# glitch_delay.net
KiCad netlist of a schematic drawn in EAGLE
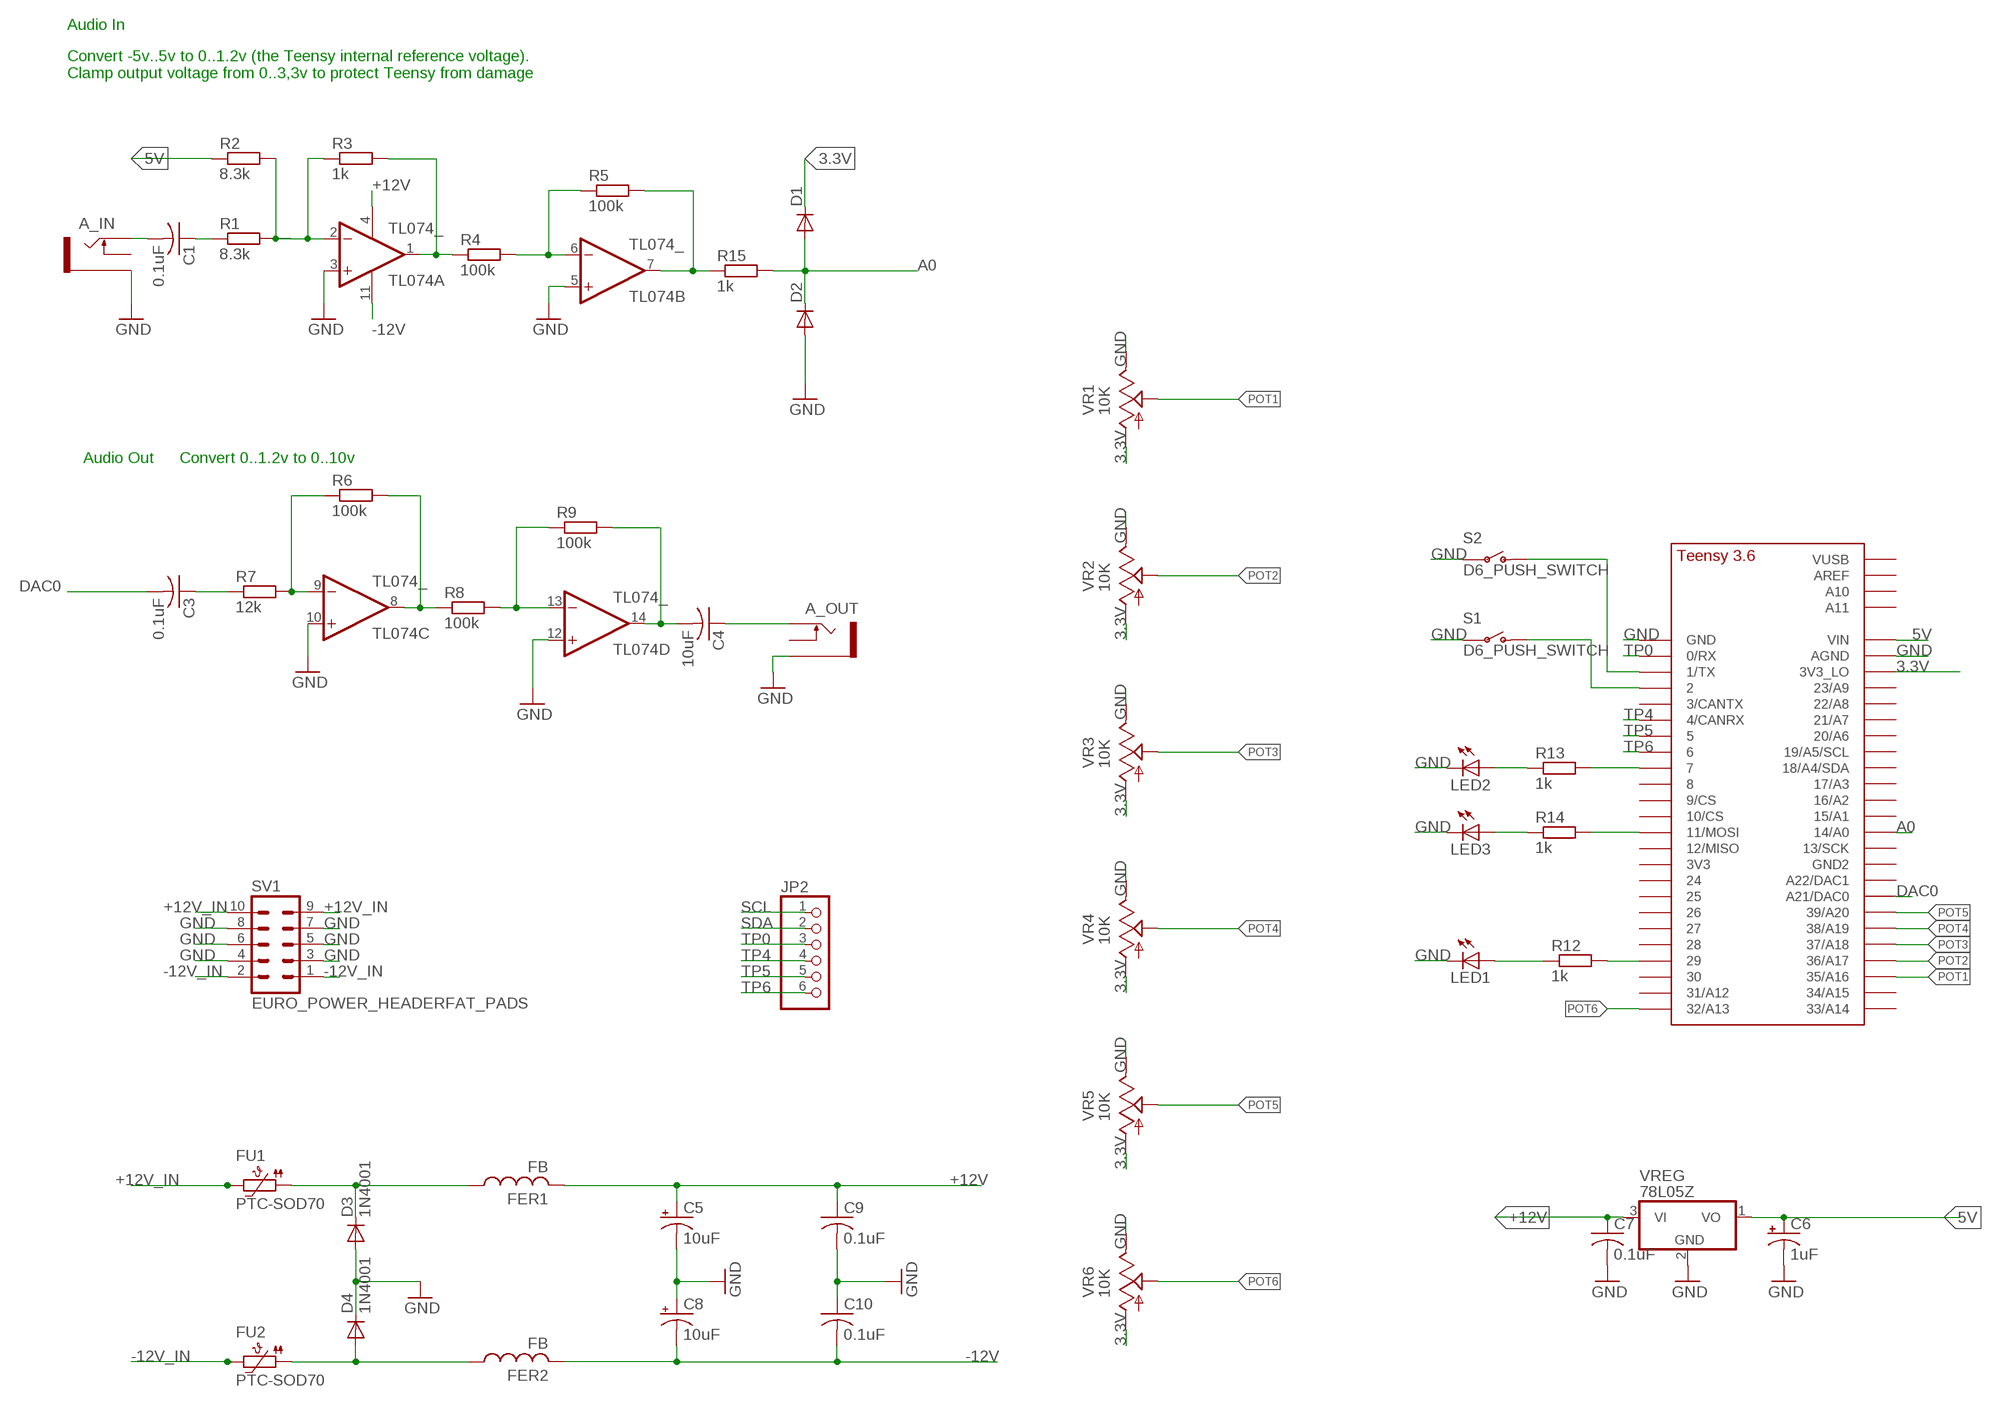
[diagram p0: schematic, sheet 1]

(export (version "E")
  (design (tool "Eeschema 10.0.6"))
  (components
    (comp (ref "A_IN")
      (value "THONKICONNNEW")
      (footprint "eagle-import:WQP-PJ301M-12_JACK")
      (libsource (lib "eagle-import") (part "THONKICONNNEW"))
    )
    (comp (ref "A_OUT")
      (value "THONKICONNNEW")
      (footprint "eagle-import:WQP-PJ301M-12_JACK")
      (libsource (lib "eagle-import") (part "THONKICONNNEW"))
    )
    (comp (ref "C1")
      (value "0.1uF")
      (footprint "eagle-import:C025-030X050")
      (libsource (lib "eagle-import") (part "C-US025-030X050"))
    )
    (comp (ref "C3")
      (value "0.1uF")
      (footprint "eagle-import:C025-030X050")
      (libsource (lib "eagle-import") (part "C-US025-030X050"))
    )
    (comp (ref "C4")
      (value "10uF")
      (footprint "eagle-import:C025-030X050")
      (libsource (lib "eagle-import") (part "C-US025-030X050"))
    )
    (comp (ref "C5")
      (value "10uF")
      (footprint "eagle-import:E2,5-6E")
      (libsource (lib "eagle-import") (part "CPOL-USE2,5-6E"))
    )
    (comp (ref "C6")
      (value "1uF")
      (footprint "eagle-import:E2,5-7")
      (libsource (lib "eagle-import") (part "CPOL-USE2.5-7"))
    )
    (comp (ref "C7")
      (value "0.1uF")
      (footprint "eagle-import:C025-030X050")
      (libsource (lib "eagle-import") (part "C-US025-030X050"))
    )
    (comp (ref "C8")
      (value "10uF")
      (footprint "eagle-import:E2,5-6E")
      (libsource (lib "eagle-import") (part "CPOL-USE2,5-6E"))
    )
    (comp (ref "C9")
      (value "0.1uF")
      (footprint "eagle-import:C025-030X050")
      (libsource (lib "eagle-import") (part "C-US025-030X050"))
    )
    (comp (ref "C10")
      (value "0.1uF")
      (footprint "eagle-import:C025-030X050")
      (libsource (lib "eagle-import") (part "C-US025-030X050"))
    )
    (comp (ref "D1")
      (value "SMALL_DIODEDO35-7")
      (footprint "eagle-import:DO35-7")
      (libsource (lib "eagle-import") (part "SMALL_DIODEDO35-7"))
    )
    (comp (ref "D2")
      (value "SMALL_DIODEDO35-7")
      (footprint "eagle-import:DO35-7")
      (libsource (lib "eagle-import") (part "SMALL_DIODEDO35-7"))
    )
    (comp (ref "D3")
      (value "1N4001")
      (footprint "eagle-import:DO41-10")
      (libsource (lib "eagle-import") (part "1N4004"))
    )
    (comp (ref "D4")
      (value "1N4001")
      (footprint "eagle-import:DO41-10")
      (libsource (lib "eagle-import") (part "1N4004"))
    )
    (comp (ref "FER1")
      (value "FB")
      (footprint "eagle-import:FB")
      (libsource (lib "eagle-import") (part "FB"))
    )
    (comp (ref "FER2")
      (value "FB")
      (footprint "eagle-import:FB")
      (libsource (lib "eagle-import") (part "FB"))
    )
    (comp (ref "FU1")
      (value "PTC-SOD70")
      (footprint "eagle-import:SOD70")
      (libsource (lib "eagle-import") (part "PTC-SOD70"))
    )
    (comp (ref "FU2")
      (value "PTC-SOD70")
      (footprint "eagle-import:SOD70")
      (libsource (lib "eagle-import") (part "PTC-SOD70"))
    )
    (comp (ref "JP2")
      (value "PINHD-1X6")
      (footprint "eagle-import:1X06")
      (libsource (lib "eagle-import") (part "PINHD-1X6"))
    )
    (comp (ref "LED1")
      (value "LED3MM")
      (footprint "eagle-import:LED3MM")
      (libsource (lib "eagle-import") (part "LED3MM"))
    )
    (comp (ref "LED2")
      (value "LED3MM")
      (footprint "eagle-import:LED3MM")
      (libsource (lib "eagle-import") (part "LED3MM"))
    )
    (comp (ref "LED3")
      (value "LED3MM")
      (footprint "eagle-import:LED3MM")
      (libsource (lib "eagle-import") (part "LED3MM"))
    )
    (comp (ref "R1")
      (value "8.3k")
      (footprint "eagle-import:7MM_RESISTOR")
      (libsource (lib "eagle-import") (part "RESISTOR7MM"))
    )
    (comp (ref "R2")
      (value "8.3k")
      (footprint "eagle-import:7MM_RESISTOR")
      (libsource (lib "eagle-import") (part "RESISTOR7MM"))
    )
    (comp (ref "R3")
      (value "1k")
      (footprint "eagle-import:7MM_RESISTOR")
      (libsource (lib "eagle-import") (part "RESISTOR7MM"))
    )
    (comp (ref "R4")
      (value "100k")
      (footprint "eagle-import:7MM_RESISTOR")
      (libsource (lib "eagle-import") (part "RESISTOR7MM"))
    )
    (comp (ref "R5")
      (value "100k")
      (footprint "eagle-import:7MM_RESISTOR")
      (libsource (lib "eagle-import") (part "RESISTOR7MM"))
    )
    (comp (ref "R6")
      (value "100k")
      (footprint "eagle-import:7MM_RESISTOR")
      (libsource (lib "eagle-import") (part "RESISTOR7MM"))
    )
    (comp (ref "R7")
      (value "12k")
      (footprint "eagle-import:7MM_RESISTOR")
      (libsource (lib "eagle-import") (part "RESISTOR7MM"))
    )
    (comp (ref "R8")
      (value "100k")
      (footprint "eagle-import:7MM_RESISTOR")
      (libsource (lib "eagle-import") (part "RESISTOR7MM"))
    )
    (comp (ref "R9")
      (value "100k")
      (footprint "eagle-import:7MM_RESISTOR")
      (libsource (lib "eagle-import") (part "RESISTOR7MM"))
    )
    (comp (ref "R12")
      (value "1k")
      (footprint "eagle-import:7MM_RESISTOR")
      (libsource (lib "eagle-import") (part "RESISTOR7MM"))
    )
    (comp (ref "R13")
      (value "1k")
      (footprint "eagle-import:7MM_RESISTOR")
      (libsource (lib "eagle-import") (part "RESISTOR7MM"))
    )
    (comp (ref "R14")
      (value "1k")
      (footprint "eagle-import:7MM_RESISTOR")
      (libsource (lib "eagle-import") (part "RESISTOR7MM"))
    )
    (comp (ref "R15")
      (value "1k")
      (footprint "eagle-import:7MM_RESISTOR")
      (libsource (lib "eagle-import") (part "RESISTOR7MM"))
    )
    (comp (ref "S1")
      (value "D6_PUSH_SWITCH")
      (footprint "eagle-import:D6_PUSH_SWITCH")
      (libsource (lib "eagle-import") (part "D6_PUSH_SWITCH"))
    )
    (comp (ref "S2")
      (value "D6_PUSH_SWITCH")
      (footprint "eagle-import:D6_PUSH_SWITCH")
      (libsource (lib "eagle-import") (part "D6_PUSH_SWITCH"))
    )
    (comp (ref "SV1")
      (value "EURO_POWER_HEADERFAT_PADS")
      (footprint "eagle-import:EURO_PWR_HEADER_FAT")
      (libsource (lib "eagle-import") (part "EURO_POWER_HEADERFAT_PADS"))
    )
    (comp (ref "TL074")
      (value "TL074_")
      (footprint "eagle-import:DIL14")
      (libsource (lib "eagle-import") (part "TL074_"))
    )
    (comp (ref "U$1")
      (value "TEENSY_3.5/3.6_BASIC")
      (footprint "eagle-import:TEENSY_3.5_3.6_BASIC")
      (libsource (lib "eagle-import") (part "TEENSY_3.5/3.6_BASIC"))
    )
    (comp (ref "VR1")
      (value "10K")
      (footprint "eagle-import:9MM_SNAP-IN_POT")
      (libsource (lib "eagle-import") (part "9MM_SNAP-IN_POT_"))
    )
    (comp (ref "VR2")
      (value "10K")
      (footprint "eagle-import:9MM_SNAP-IN_POT")
      (libsource (lib "eagle-import") (part "9MM_SNAP-IN_POT_"))
    )
    (comp (ref "VR3")
      (value "10K")
      (footprint "eagle-import:9MM_SNAP-IN_POT")
      (libsource (lib "eagle-import") (part "9MM_SNAP-IN_POT_"))
    )
    (comp (ref "VR4")
      (value "10K")
      (footprint "eagle-import:9MM_SNAP-IN_POT")
      (libsource (lib "eagle-import") (part "9MM_SNAP-IN_POT_"))
    )
    (comp (ref "VR5")
      (value "10K")
      (footprint "eagle-import:9MM_SNAP-IN_POT")
      (libsource (lib "eagle-import") (part "9MM_SNAP-IN_POT_"))
    )
    (comp (ref "VR6")
      (value "10K")
      (footprint "eagle-import:9MM_SNAP-IN_POT")
      (libsource (lib "eagle-import") (part "9MM_SNAP-IN_POT_"))
    )
    (comp (ref "VREG")
      (value "78L05Z")
      (footprint "eagle-import:TO92")
      (libsource (lib "eagle-import") (part "78ZL05"))
    )
  )
  (nets
    (net (code "1") (name "+12V") (class "Default")
      (node (ref "C5") (pin "+") (pinfunction "+_+") (pintype "passive"))
      (node (ref "C7") (pin "1") (pinfunction "1_1") (pintype "passive"))
      (node (ref "C9") (pin "1") (pinfunction "1_1") (pintype "passive"))
      (node (ref "FER1") (pin "P$2") (pinfunction "2_P$2") (pintype "passive"))
      (node (ref "TL074") (pin "4") (pinfunction "V+_4") (pintype "power_in"))
      (node (ref "VREG") (pin "3") (pinfunction "VI_3") (pintype "input"))
    )
    (net (code "2") (name "/+12V_IN") (class "Default")
      (node (ref "FU1") (pin "2") (pinfunction "2_2") (pintype "passive"))
      (node (ref "SV1") (pin "10") (pinfunction "10_10") (pintype "passive"))
      (node (ref "SV1") (pin "9") (pinfunction "9_9") (pintype "passive"))
    )
    (net (code "3") (name "/-12V") (class "Default")
      (node (ref "C10") (pin "2") (pinfunction "2_2") (pintype "passive"))
      (node (ref "C8") (pin "-") (pinfunction "-_-") (pintype "passive"))
      (node (ref "FER2") (pin "P$2") (pinfunction "2_P$2") (pintype "passive"))
      (node (ref "TL074") (pin "11") (pinfunction "V-_11") (pintype "power_in"))
    )
    (net (code "4") (name "/-12V_IN") (class "Default")
      (node (ref "FU2") (pin "2") (pinfunction "2_2") (pintype "passive"))
      (node (ref "SV1") (pin "1") (pinfunction "1_1") (pintype "passive"))
      (node (ref "SV1") (pin "2") (pinfunction "2_2") (pintype "passive"))
    )
    (net (code "5") (name "/A0") (class "Default")
      (node (ref "D1") (pin "A") (pinfunction "A_A") (pintype "passive"))
      (node (ref "D2") (pin "C") (pinfunction "C_C") (pintype "passive"))
      (node (ref "R15") (pin "2") (pinfunction "2_2") (pintype "passive"))
      (node (ref "U$1") (pin "14/A0") (pinfunction "14/A0_14/A0") (pintype "bidirectional"))
    )
    (net (code "6") (name "/DAC0") (class "Default")
      (node (ref "C3") (pin "2") (pinfunction "2_2") (pintype "passive"))
      (node (ref "U$1") (pin "21/DAC0") (pinfunction "A21/DAC0_21/DAC0") (pintype "bidirectional"))
    )
    (net (code "7") (name "/SCL") (class "Default")
      (node (ref "JP2") (pin "1") (pinfunction "1_1") (pintype "passive"))
    )
    (net (code "8") (name "/SDA") (class "Default")
      (node (ref "JP2") (pin "2") (pinfunction "2_2") (pintype "passive"))
    )
    (net (code "9") (name "/TP0") (class "Default")
      (node (ref "JP2") (pin "3") (pinfunction "3_3") (pintype "passive"))
      (node (ref "U$1") (pin "0/RX") (pinfunction "0/RX_0/RX") (pintype "bidirectional"))
    )
    (net (code "10") (name "/TP4") (class "Default")
      (node (ref "JP2") (pin "4") (pinfunction "4_4") (pintype "passive"))
      (node (ref "U$1") (pin "4/CANRX") (pinfunction "4/CANRX_4/CANRX") (pintype "bidirectional"))
    )
    (net (code "11") (name "/TP5") (class "Default")
      (node (ref "JP2") (pin "5") (pinfunction "5_5") (pintype "passive"))
      (node (ref "U$1") (pin "5") (pinfunction "5_5") (pintype "bidirectional"))
    )
    (net (code "12") (name "/TP6") (class "Default")
      (node (ref "JP2") (pin "6") (pinfunction "6_6") (pintype "passive"))
      (node (ref "U$1") (pin "6") (pinfunction "6_6") (pintype "bidirectional"))
    )
    (net (code "13") (name "3.3V") (class "Default")
      (node (ref "D1") (pin "C") (pinfunction "C_C") (pintype "passive"))
      (node (ref "U$1") (pin "3V3_LO") (pinfunction "3V3_LO_3V3_LO") (pintype "bidirectional"))
      (node (ref "VR1") (pin "1") (pinfunction "A_1") (pintype "passive"))
      (node (ref "VR2") (pin "1") (pinfunction "A_1") (pintype "passive"))
      (node (ref "VR3") (pin "1") (pinfunction "A_1") (pintype "passive"))
      (node (ref "VR4") (pin "1") (pinfunction "A_1") (pintype "passive"))
      (node (ref "VR5") (pin "1") (pinfunction "A_1") (pintype "passive"))
      (node (ref "VR6") (pin "1") (pinfunction "A_1") (pintype "passive"))
    )
    (net (code "14") (name "5V") (class "Default")
      (node (ref "C6") (pin "+") (pinfunction "+_+") (pintype "passive"))
      (node (ref "R2") (pin "1") (pinfunction "1_1") (pintype "passive"))
      (node (ref "U$1") (pin "VIN") (pinfunction "VIN_VIN") (pintype "bidirectional"))
      (node (ref "VREG") (pin "1") (pinfunction "VO_1") (pintype "passive"))
    )
    (net (code "15") (name "GND") (class "Default")
      (node (ref "A_IN") (pin "P$3_SLEEVE") (pinfunction "SLEEVE_P$3_SLEEVE") (pintype "passive"))
      (node (ref "A_OUT") (pin "P$3_SLEEVE") (pinfunction "SLEEVE_P$3_SLEEVE") (pintype "passive"))
      (node (ref "C10") (pin "1") (pinfunction "1_1") (pintype "passive"))
      (node (ref "C5") (pin "-") (pinfunction "-_-") (pintype "passive"))
      (node (ref "C6") (pin "-") (pinfunction "-_-") (pintype "passive"))
      (node (ref "C7") (pin "2") (pinfunction "2_2") (pintype "passive"))
      (node (ref "C8") (pin "+") (pinfunction "+_+") (pintype "passive"))
      (node (ref "C9") (pin "2") (pinfunction "2_2") (pintype "passive"))
      (node (ref "D2") (pin "A") (pinfunction "A_A") (pintype "passive"))
      (node (ref "D3") (pin "A") (pinfunction "A_A") (pintype "passive"))
      (node (ref "D4") (pin "C") (pinfunction "C_C") (pintype "passive"))
      (node (ref "LED1") (pin "K") (pinfunction "C_K") (pintype "passive"))
      (node (ref "LED2") (pin "K") (pinfunction "C_K") (pintype "passive"))
      (node (ref "LED3") (pin "K") (pinfunction "C_K") (pintype "passive"))
      (node (ref "S1") (pin "P$3") (pinfunction "P_P$3") (pintype "passive"))
      (node (ref "S1") (pin "P$4") (pinfunction "P_P$4") (pintype "passive"))
      (node (ref "S2") (pin "P$3") (pinfunction "P_P$3") (pintype "passive"))
      (node (ref "S2") (pin "P$4") (pinfunction "P_P$4") (pintype "passive"))
      (node (ref "SV1") (pin "3") (pinfunction "3_3") (pintype "passive"))
      (node (ref "SV1") (pin "4") (pinfunction "4_4") (pintype "passive"))
      (node (ref "SV1") (pin "5") (pinfunction "5_5") (pintype "passive"))
      (node (ref "SV1") (pin "6") (pinfunction "6_6") (pintype "passive"))
      (node (ref "SV1") (pin "7") (pinfunction "7_7") (pintype "passive"))
      (node (ref "SV1") (pin "8") (pinfunction "8_8") (pintype "passive"))
      (node (ref "TL074") (pin "10") (pinfunction "+IN_10") (pintype "input"))
      (node (ref "TL074") (pin "12") (pinfunction "+IN_12") (pintype "input"))
      (node (ref "TL074") (pin "3") (pinfunction "+IN_3") (pintype "input"))
      (node (ref "TL074") (pin "5") (pinfunction "+IN_5") (pintype "input"))
      (node (ref "U$1") (pin "AGND") (pinfunction "AGND_AGND") (pintype "bidirectional"))
      (node (ref "U$1") (pin "GND") (pinfunction "GND_GND") (pintype "bidirectional"))
      (node (ref "VR1") (pin "3") (pinfunction "E_3") (pintype "passive"))
      (node (ref "VR2") (pin "3") (pinfunction "E_3") (pintype "passive"))
      (node (ref "VR3") (pin "3") (pinfunction "E_3") (pintype "passive"))
      (node (ref "VR4") (pin "3") (pinfunction "E_3") (pintype "passive"))
      (node (ref "VR5") (pin "3") (pinfunction "E_3") (pintype "passive"))
      (node (ref "VR6") (pin "3") (pinfunction "E_3") (pintype "passive"))
      (node (ref "VREG") (pin "2") (pinfunction "GND_2") (pintype "passive"))
    )
    (net (code "16") (name "Net-(A_IN-TIP)") (class "Default")
      (node (ref "A_IN") (pin "P$1_TIP") (pinfunction "TIP_P$1_TIP") (pintype "passive"))
      (node (ref "C1") (pin "2") (pinfunction "2_2") (pintype "passive"))
    )
    (net (code "17") (name "Net-(A_OUT-TIP)") (class "Default")
      (node (ref "A_OUT") (pin "P$1_TIP") (pinfunction "TIP_P$1_TIP") (pintype "passive"))
      (node (ref "C4") (pin "1") (pinfunction "1_1") (pintype "passive"))
    )
    (net (code "18") (name "Net-(C1-Pad1)") (class "Default")
      (node (ref "C1") (pin "1") (pinfunction "1_1") (pintype "passive"))
      (node (ref "R1") (pin "1") (pinfunction "1_1") (pintype "passive"))
    )
    (net (code "19") (name "Net-(C3-Pad1)") (class "Default")
      (node (ref "C3") (pin "1") (pinfunction "1_1") (pintype "passive"))
      (node (ref "R7") (pin "1") (pinfunction "1_1") (pintype "passive"))
    )
    (net (code "20") (name "Net-(FER1-1)") (class "Default")
      (node (ref "D3") (pin "C") (pinfunction "C_C") (pintype "passive"))
      (node (ref "FER1") (pin "P$1") (pinfunction "1_P$1") (pintype "passive"))
      (node (ref "FU1") (pin "1") (pinfunction "1_1") (pintype "passive"))
    )
    (net (code "21") (name "Net-(FER2-1)") (class "Default")
      (node (ref "D4") (pin "A") (pinfunction "A_A") (pintype "passive"))
      (node (ref "FER2") (pin "P$1") (pinfunction "1_P$1") (pintype "passive"))
      (node (ref "FU2") (pin "1") (pinfunction "1_1") (pintype "passive"))
    )
    (net (code "22") (name "Net-(LED1-PadA)") (class "Default")
      (node (ref "LED1") (pin "A") (pinfunction "A_A") (pintype "passive"))
      (node (ref "R12") (pin "1") (pinfunction "1_1") (pintype "passive"))
    )
    (net (code "23") (name "Net-(LED2-PadA)") (class "Default")
      (node (ref "LED2") (pin "A") (pinfunction "A_A") (pintype "passive"))
      (node (ref "R13") (pin "1") (pinfunction "1_1") (pintype "passive"))
    )
    (net (code "24") (name "Net-(LED3-PadA)") (class "Default")
      (node (ref "LED3") (pin "A") (pinfunction "A_A") (pintype "passive"))
      (node (ref "R14") (pin "1") (pinfunction "1_1") (pintype "passive"))
    )
    (net (code "25") (name "Net-(R12-Pad2)") (class "Default")
      (node (ref "R12") (pin "2") (pinfunction "2_2") (pintype "passive"))
      (node (ref "U$1") (pin "29") (pinfunction "29_29") (pintype "bidirectional"))
    )
    (net (code "26") (name "Net-(R13-Pad2)") (class "Default")
      (node (ref "R13") (pin "2") (pinfunction "2_2") (pintype "passive"))
      (node (ref "U$1") (pin "7") (pinfunction "7_7") (pintype "bidirectional"))
    )
    (net (code "27") (name "Net-(R14-Pad2)") (class "Default")
      (node (ref "R14") (pin "2") (pinfunction "2_2") (pintype "passive"))
      (node (ref "U$1") (pin "11/MOSI") (pinfunction "11/MOSI_11/MOSI") (pintype "bidirectional"))
    )
    (net (code "28") (name "Net-(S1-O-PadP$1)") (class "Default")
      (node (ref "S1") (pin "P$1") (pinfunction "O_P$1") (pintype "passive"))
      (node (ref "S1") (pin "P$2") (pinfunction "O_P$2") (pintype "passive"))
      (node (ref "U$1") (pin "2") (pinfunction "2_2") (pintype "bidirectional"))
    )
    (net (code "29") (name "Net-(S2-O-PadP$1)") (class "Default")
      (node (ref "S2") (pin "P$1") (pinfunction "O_P$1") (pintype "passive"))
      (node (ref "S2") (pin "P$2") (pinfunction "O_P$2") (pintype "passive"))
      (node (ref "U$1") (pin "1/TX") (pinfunction "1/TX_1/TX") (pintype "bidirectional"))
    )
    (net (code "30") (name "Net-(TL074A--IN)") (class "Default")
      (node (ref "R1") (pin "2") (pinfunction "2_2") (pintype "passive"))
      (node (ref "R2") (pin "2") (pinfunction "2_2") (pintype "passive"))
      (node (ref "R3") (pin "1") (pinfunction "1_1") (pintype "passive"))
      (node (ref "TL074") (pin "2") (pinfunction "-IN_2") (pintype "input"))
    )
    (net (code "31") (name "Net-(TL074A-OUT)") (class "Default")
      (node (ref "R3") (pin "2") (pinfunction "2_2") (pintype "passive"))
      (node (ref "R4") (pin "1") (pinfunction "1_1") (pintype "passive"))
      (node (ref "TL074") (pin "1") (pinfunction "OUT_1") (pintype "output"))
    )
    (net (code "32") (name "Net-(TL074B--IN)") (class "Default")
      (node (ref "R4") (pin "2") (pinfunction "2_2") (pintype "passive"))
      (node (ref "R5") (pin "1") (pinfunction "1_1") (pintype "passive"))
      (node (ref "TL074") (pin "6") (pinfunction "-IN_6") (pintype "input"))
    )
    (net (code "33") (name "Net-(TL074B-OUT)") (class "Default")
      (node (ref "R15") (pin "1") (pinfunction "1_1") (pintype "passive"))
      (node (ref "R5") (pin "2") (pinfunction "2_2") (pintype "passive"))
      (node (ref "TL074") (pin "7") (pinfunction "OUT_7") (pintype "output"))
    )
    (net (code "34") (name "Net-(TL074C--IN)") (class "Default")
      (node (ref "R6") (pin "1") (pinfunction "1_1") (pintype "passive"))
      (node (ref "R7") (pin "2") (pinfunction "2_2") (pintype "passive"))
      (node (ref "TL074") (pin "9") (pinfunction "-IN_9") (pintype "input"))
    )
    (net (code "35") (name "Net-(TL074C-OUT)") (class "Default")
      (node (ref "R6") (pin "2") (pinfunction "2_2") (pintype "passive"))
      (node (ref "R8") (pin "1") (pinfunction "1_1") (pintype "passive"))
      (node (ref "TL074") (pin "8") (pinfunction "OUT_8") (pintype "output"))
    )
    (net (code "36") (name "Net-(TL074D--IN)") (class "Default")
      (node (ref "R8") (pin "2") (pinfunction "2_2") (pintype "passive"))
      (node (ref "R9") (pin "1") (pinfunction "1_1") (pintype "passive"))
      (node (ref "TL074") (pin "13") (pinfunction "-IN_13") (pintype "input"))
    )
    (net (code "37") (name "Net-(TL074D-OUT)") (class "Default")
      (node (ref "C4") (pin "2") (pinfunction "2_2") (pintype "passive"))
      (node (ref "R9") (pin "2") (pinfunction "2_2") (pintype "passive"))
      (node (ref "TL074") (pin "14") (pinfunction "OUT_14") (pintype "output"))
    )
    (net (code "38") (name "POT1") (class "Default")
      (node (ref "U$1") (pin "35/A16") (pinfunction "35/A16_35/A16") (pintype "bidirectional"))
      (node (ref "VR1") (pin "2") (pinfunction "S_2") (pintype "passive"))
    )
    (net (code "39") (name "POT2") (class "Default")
      (node (ref "U$1") (pin "36/A17") (pinfunction "36/A17_36/A17") (pintype "bidirectional"))
      (node (ref "VR2") (pin "2") (pinfunction "S_2") (pintype "passive"))
    )
    (net (code "40") (name "POT3") (class "Default")
      (node (ref "U$1") (pin "37/A18") (pinfunction "37/A18_37/A18") (pintype "bidirectional"))
      (node (ref "VR3") (pin "2") (pinfunction "S_2") (pintype "passive"))
    )
    (net (code "41") (name "POT4") (class "Default")
      (node (ref "U$1") (pin "38/A19") (pinfunction "38/A19_38/A19") (pintype "bidirectional"))
      (node (ref "VR4") (pin "2") (pinfunction "S_2") (pintype "passive"))
    )
    (net (code "42") (name "POT5") (class "Default")
      (node (ref "U$1") (pin "39/A20") (pinfunction "39/A20_39/A20") (pintype "bidirectional"))
      (node (ref "VR5") (pin "2") (pinfunction "S_2") (pintype "passive"))
    )
    (net (code "43") (name "POT6") (class "Default")
      (node (ref "U$1") (pin "32/A13") (pinfunction "32/A13_32/A13") (pintype "bidirectional"))
      (node (ref "VR6") (pin "2") (pinfunction "S_2") (pintype "passive"))
    )
    (net (code "44") (name "unconnected-(A_IN-SWITCH-PadP$2_SWITCH)") (class "Default")
      (node (ref "A_IN") (pin "P$2_SWITCH") (pinfunction "SWITCH_P$2_SWITCH") (pintype "passive"))
    )
    (net (code "45") (name "unconnected-(A_OUT-SWITCH-PadP$2_SWITCH)") (class "Default")
      (node (ref "A_OUT") (pin "P$2_SWITCH") (pinfunction "SWITCH_P$2_SWITCH") (pintype "passive"))
    )
    (net (code "46") (name "unconnected-(U$1-Pad3V3)") (class "Default")
      (node (ref "U$1") (pin "3V3") (pinfunction "3V3_3V3") (pintype "bidirectional"))
    )
    (net (code "47") (name "unconnected-(U$1-Pad3{slash}CANTX)") (class "Default")
      (node (ref "U$1") (pin "3/CANTX") (pinfunction "3/CANTX_3/CANTX") (pintype "bidirectional"))
    )
    (net (code "48") (name "unconnected-(U$1-Pad8)") (class "Default")
      (node (ref "U$1") (pin "8") (pinfunction "8_8") (pintype "bidirectional"))
    )
    (net (code "49") (name "unconnected-(U$1-Pad9{slash}CS)") (class "Default")
      (node (ref "U$1") (pin "9/CS") (pinfunction "9/CS_9/CS") (pintype "bidirectional"))
    )
    (net (code "50") (name "unconnected-(U$1-Pad10{slash}CS)") (class "Default")
      (node (ref "U$1") (pin "10/CS") (pinfunction "10/CS_10/CS") (pintype "bidirectional"))
    )
    (net (code "51") (name "unconnected-(U$1-Pad12{slash}MISO)") (class "Default")
      (node (ref "U$1") (pin "12/MISO") (pinfunction "12/MISO_12/MISO") (pintype "bidirectional"))
    )
    (net (code "52") (name "unconnected-(U$1-Pad13{slash}SCK)") (class "Default")
      (node (ref "U$1") (pin "13/SCK") (pinfunction "13/SCK_13/SCK") (pintype "bidirectional"))
    )
    (net (code "53") (name "unconnected-(U$1-Pad15{slash}A1)") (class "Default")
      (node (ref "U$1") (pin "15/A1") (pinfunction "15/A1_15/A1") (pintype "bidirectional"))
    )
    (net (code "54") (name "unconnected-(U$1-Pad16{slash}A2)") (class "Default")
      (node (ref "U$1") (pin "16/A2") (pinfunction "16/A2_16/A2") (pintype "bidirectional"))
    )
    (net (code "55") (name "unconnected-(U$1-Pad17{slash}A3)") (class "Default")
      (node (ref "U$1") (pin "17/A3") (pinfunction "17/A3_17/A3") (pintype "bidirectional"))
    )
    (net (code "56") (name "unconnected-(U$1-Pad18{slash}A4{slash}SDA)") (class "Default")
      (node (ref "U$1") (pin "18/A4/SDA") (pinfunction "18/A4/SDA_18/A4/SDA") (pintype "bidirectional"))
    )
    (net (code "57") (name "unconnected-(U$1-Pad19{slash}A5{slash}SCL)") (class "Default")
      (node (ref "U$1") (pin "19/A5/SCL") (pinfunction "19/A5/SCL_19/A5/SCL") (pintype "bidirectional"))
    )
    (net (code "58") (name "unconnected-(U$1-Pad20{slash}A6)") (class "Default")
      (node (ref "U$1") (pin "20/A6") (pinfunction "20/A6_20/A6") (pintype "bidirectional"))
    )
    (net (code "59") (name "unconnected-(U$1-Pad21{slash}A7)") (class "Default")
      (node (ref "U$1") (pin "21/A7") (pinfunction "21/A7_21/A7") (pintype "bidirectional"))
    )
    (net (code "60") (name "unconnected-(U$1-Pad22{slash}A8)") (class "Default")
      (node (ref "U$1") (pin "22/A8") (pinfunction "22/A8_22/A8") (pintype "bidirectional"))
    )
    (net (code "61") (name "unconnected-(U$1-Pad23{slash}A9)") (class "Default")
      (node (ref "U$1") (pin "23/A9") (pinfunction "23/A9_23/A9") (pintype "bidirectional"))
    )
    (net (code "62") (name "unconnected-(U$1-Pad24)") (class "Default")
      (node (ref "U$1") (pin "24") (pinfunction "24_24") (pintype "bidirectional"))
    )
    (net (code "63") (name "unconnected-(U$1-Pad25)") (class "Default")
      (node (ref "U$1") (pin "25") (pinfunction "25_25") (pintype "bidirectional"))
    )
    (net (code "64") (name "unconnected-(U$1-Pad26)") (class "Default")
      (node (ref "U$1") (pin "26") (pinfunction "26_26") (pintype "bidirectional"))
    )
    (net (code "65") (name "unconnected-(U$1-Pad27)") (class "Default")
      (node (ref "U$1") (pin "27") (pinfunction "27_27") (pintype "bidirectional"))
    )
    (net (code "66") (name "unconnected-(U$1-Pad28)") (class "Default")
      (node (ref "U$1") (pin "28") (pinfunction "28_28") (pintype "bidirectional"))
    )
    (net (code "67") (name "unconnected-(U$1-Pad30)") (class "Default")
      (node (ref "U$1") (pin "30") (pinfunction "30_30") (pintype "bidirectional"))
    )
    (net (code "68") (name "unconnected-(U$1-Pad31{slash}A12)") (class "Default")
      (node (ref "U$1") (pin "31/A12") (pinfunction "31/A12_31/A12") (pintype "bidirectional"))
    )
    (net (code "69") (name "unconnected-(U$1-Pad33{slash}A14)") (class "Default")
      (node (ref "U$1") (pin "33/A14") (pinfunction "33/A14_33/A14") (pintype "bidirectional"))
    )
    (net (code "70") (name "unconnected-(U$1-Pad34{slash}A15)") (class "Default")
      (node (ref "U$1") (pin "34/A15") (pinfunction "34/A15_34/A15") (pintype "bidirectional"))
    )
    (net (code "71") (name "unconnected-(U$1-PadA10)") (class "Default")
      (node (ref "U$1") (pin "A10") (pinfunction "A10_A10") (pintype "bidirectional"))
    )
    (net (code "72") (name "unconnected-(U$1-PadA11)") (class "Default")
      (node (ref "U$1") (pin "A11") (pinfunction "A11_A11") (pintype "bidirectional"))
    )
    (net (code "73") (name "unconnected-(U$1-PadA22{slash}DAC1)") (class "Default")
      (node (ref "U$1") (pin "A22/DAC1") (pinfunction "A22/DAC1_A22/DAC1") (pintype "bidirectional"))
    )
    (net (code "74") (name "unconnected-(U$1-PadAREF)") (class "Default")
      (node (ref "U$1") (pin "AREF") (pinfunction "AREF_AREF") (pintype "bidirectional"))
    )
    (net (code "75") (name "unconnected-(U$1-PadGND2)") (class "Default")
      (node (ref "U$1") (pin "GND2") (pinfunction "GND2_GND2") (pintype "bidirectional"))
    )
    (net (code "76") (name "unconnected-(U$1-PadVUSB)") (class "Default")
      (node (ref "U$1") (pin "VUSB") (pinfunction "VUSB_VUSB") (pintype "bidirectional"))
    )
  )
)
